# Trigger_Delay_Board.net
KiCad netlist of a schematic drawn in EAGLE
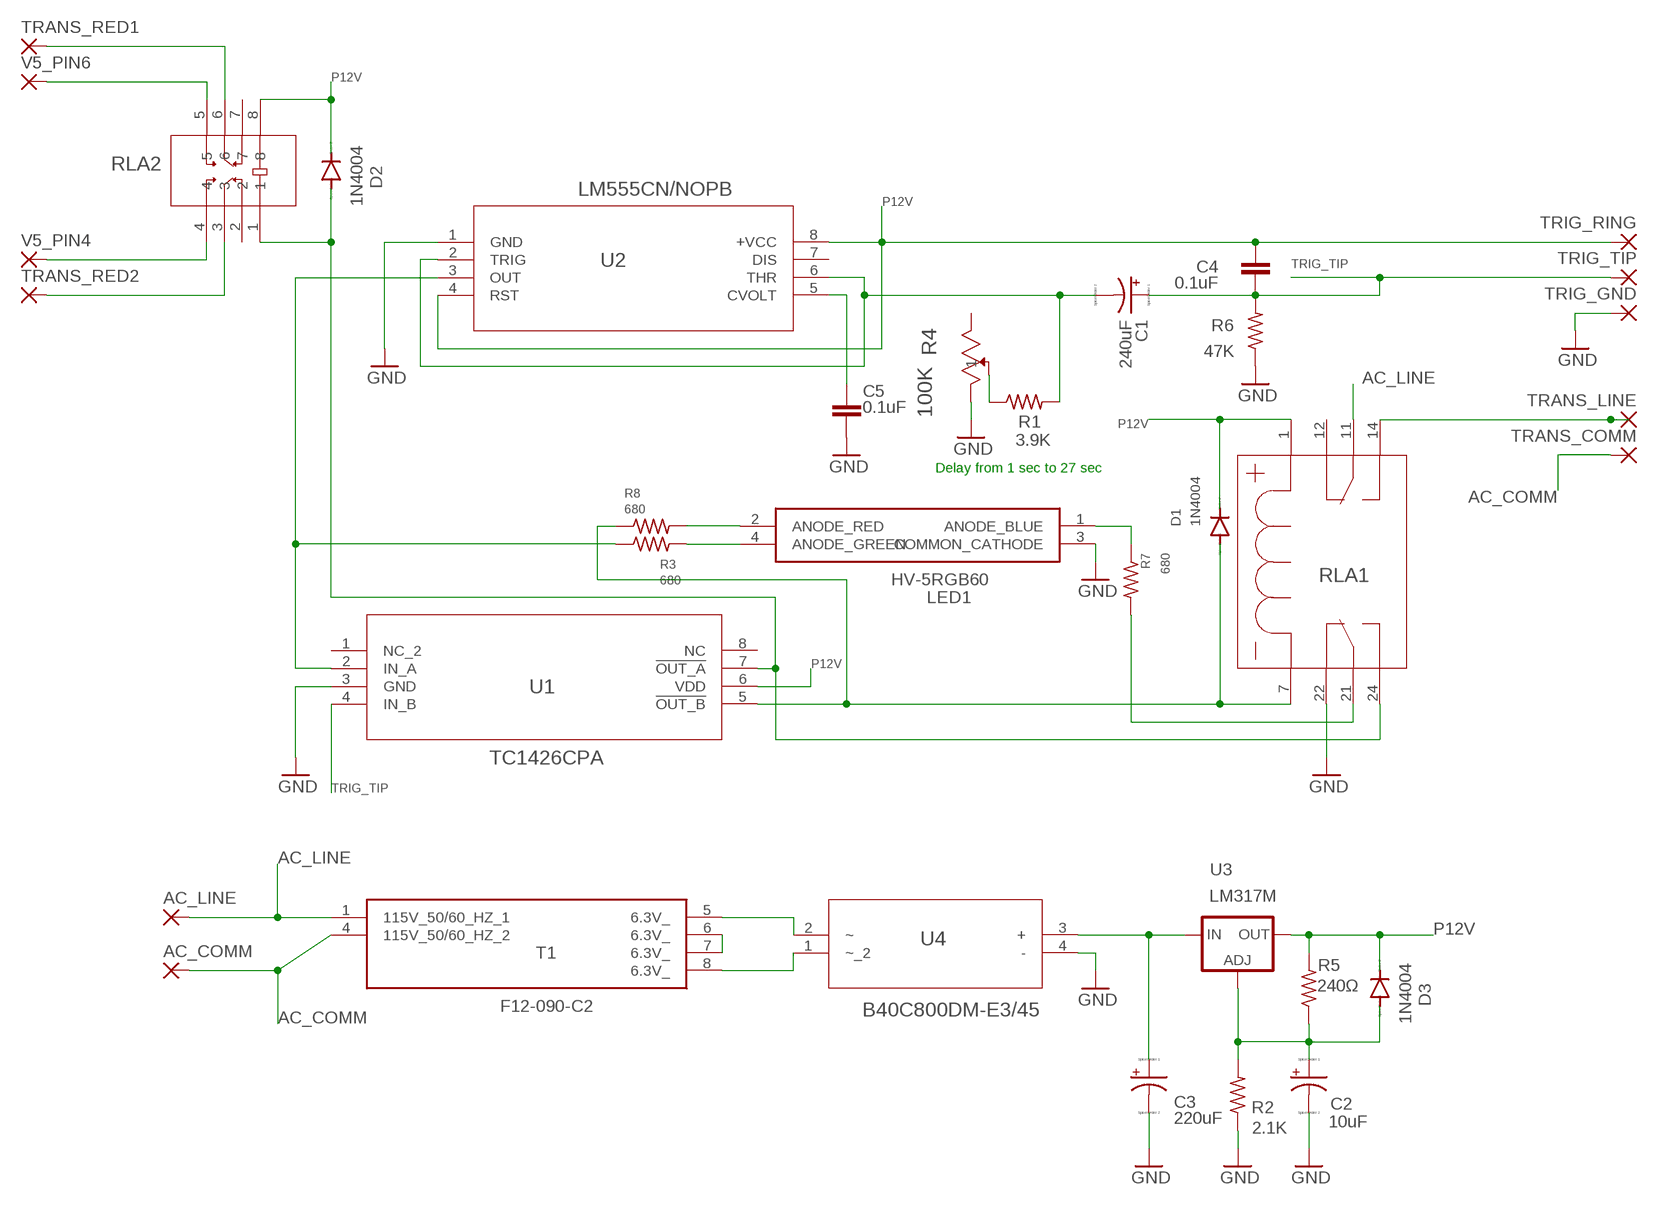
[diagram p0: schematic, sheet 1]

(export (version "E")
  (design (tool "Eeschema 10.0.6"))
  (components
    (comp (ref "AC_COMM")
      (value "3,81/1,4")
      (footprint "eagle-import:3,81_1,4")
      (libsource (lib "eagle-import") (part "3,81/1,4"))
    )
    (comp (ref "AC_LINE")
      (value "3,81/1,4")
      (footprint "eagle-import:3,81_1,4")
      (libsource (lib "eagle-import") (part "3,81/1,4"))
    )
    (comp (ref "C1")
      (value "240uF")
      (footprint "eagle-import:E1,8-4")
      (libsource (lib "eagle-import") (part "CPOL-USE1.8-4"))
    )
    (comp (ref "C2")
      (value "10uF")
      (footprint "eagle-import:E1,8-4")
      (libsource (lib "eagle-import") (part "CPOL-USE1.8-4"))
    )
    (comp (ref "C3")
      (value "220uF")
      (footprint "eagle-import:E1,8-4")
      (libsource (lib "eagle-import") (part "CPOL-USE1.8-4"))
    )
    (comp (ref "C4")
      (value "0.1uF")
      (footprint "eagle-import:C025-024X044")
      (libsource (lib "eagle-import") (part "C-EU025-024X044"))
    )
    (comp (ref "C5")
      (value "0.1uF")
      (footprint "eagle-import:C025-024X044")
      (libsource (lib "eagle-import") (part "C-EU025-024X044"))
    )
    (comp (ref "D1")
      (value "1N4004")
      (footprint "eagle-import:DO41-10")
      (libsource (lib "eagle-import") (part "1N4004"))
    )
    (comp (ref "D2")
      (value "1N4004")
      (footprint "eagle-import:DO41-10")
      (libsource (lib "eagle-import") (part "1N4004"))
    )
    (comp (ref "D3")
      (value "1N4004")
      (footprint "eagle-import:DO41-10")
      (libsource (lib "eagle-import") (part "1N4004"))
    )
    (comp (ref "LED1")
      (value "HV-5RGB60")
      (footprint "eagle-import:HV5RGB25")
      (fields (field (name "MOUSER_PART_NUMBER") "743-HV-5RGB60"))
      (libsource (lib "eagle-import") (part "HV-5RGB60"))
    )
    (comp (ref "R1")
      (value "3.9K")
      (footprint "eagle-import:0207_10")
      (libsource (lib "eagle-import") (part "R-US_0207/10"))
    )
    (comp (ref "R2")
      (value "2.1K")
      (footprint "eagle-import:0207_10")
      (libsource (lib "eagle-import") (part "R-US_0207/10"))
    )
    (comp (ref "R3")
      (value "680")
      (footprint "eagle-import:0207_10")
      (libsource (lib "eagle-import") (part "R-US_0207/10"))
    )
    (comp (ref "R4")
      (value "100K")
      (footprint "eagle-import:RES3_64W")
      (fields
        (field (name "MANUFACTURER_PART_NUMBER") "64WR100KLF")
        (field (name "COPYRIGHT") "Copyright (C) 2016 Accelerated Designs. All rights reserved")
      )
      (libsource (lib "eagle-import") (part "64WR100KLF"))
    )
    (comp (ref "R5")
      (value "240Ω")
      (footprint "eagle-import:0207_10")
      (libsource (lib "eagle-import") (part "R-US_0207/10"))
    )
    (comp (ref "R6")
      (value "47K")
      (footprint "eagle-import:0207_10")
      (libsource (lib "eagle-import") (part "R-US_0207/10"))
    )
    (comp (ref "R7")
      (value "680")
      (footprint "eagle-import:0207_10")
      (libsource (lib "eagle-import") (part "R-US_0207/10"))
    )
    (comp (ref "R8")
      (value "680")
      (footprint "eagle-import:0207_10")
      (libsource (lib "eagle-import") (part "R-US_0207/10"))
    )
    (comp (ref "RLA1")
      (value "RTE24012")
      (footprint "eagle-import:RELAY-DPDT_5MM")
      (fields (field (name "COPYRIGHT") "Copyright (C) 2016 Accelerated Designs. All rights reserved"))
      (libsource (lib "eagle-import") (part "RTE24012"))
    )
    (comp (ref "RLA2")
      (value "G2RL-2_DC12")
      (footprint "eagle-import:RELAY_G2RL-2")
      (fields
        (field (name "MANUFACTURER_PART_NUMBER") "G2RL-2 DC12")
        (field (name "COPYRIGHT") "Copyright (C) 2018 Accelerated Designs. All rights reserved")
      )
      (libsource (lib "eagle-import") (part "G2RL-2_DC12"))
    )
    (comp (ref "T1")
      (value "F12-090-C2")
      (footprint "eagle-import:F12090C2")
      (fields (field (name "MOUSER_PART_NUMBER") "553-F12-090-C2"))
      (libsource (lib "eagle-import") (part "F12-090-C2"))
    )
    (comp (ref "TRANS_COMM")
      (value "3,81/1,4")
      (footprint "eagle-import:3,81_1,4")
      (libsource (lib "eagle-import") (part "3,81/1,4"))
    )
    (comp (ref "TRANS_LINE")
      (value "3,81/1,4")
      (footprint "eagle-import:3,81_1,4")
      (libsource (lib "eagle-import") (part "3,81/1,4"))
    )
    (comp (ref "TRANS_RED1")
      (value "3,81/1,4")
      (footprint "eagle-import:3,81_1,4")
      (libsource (lib "eagle-import") (part "3,81/1,4"))
    )
    (comp (ref "TRANS_RED2")
      (value "3,81/1,4")
      (footprint "eagle-import:3,81_1,4")
      (libsource (lib "eagle-import") (part "3,81/1,4"))
    )
    (comp (ref "TRIG_GND")
      (value "3,81/1,4")
      (footprint "eagle-import:3,81_1,4")
      (libsource (lib "eagle-import") (part "3,81/1,4"))
    )
    (comp (ref "TRIG_RING")
      (value "3,81/1,4")
      (footprint "eagle-import:3,81_1,4")
      (libsource (lib "eagle-import") (part "3,81/1,4"))
    )
    (comp (ref "TRIG_TIP")
      (value "3,81/1,4")
      (footprint "eagle-import:3,81_1,4")
      (libsource (lib "eagle-import") (part "3,81/1,4"))
    )
    (comp (ref "U1")
      (value "TC1426CPA")
      (footprint "eagle-import:PDIP8_300MC")
      (libsource (lib "eagle-import") (part "TC1426CPA"))
    )
    (comp (ref "U2")
      (value "LM555CN/NOPB")
      (footprint "eagle-import:N08E")
      (libsource (lib "eagle-import") (part "LM555CN/NOPB"))
    )
    (comp (ref "U3")
      (value "LM317MB")
      (footprint "eagle-import:TO220L1")
      (fields (field (name "PARTNUMBER") "LM317M"))
      (libsource (lib "eagle-import") (part "LM317?MB"))
    )
    (comp (ref "U4")
      (value "B40C800DM-E3/45")
      (footprint "eagle-import:DIP4_DFM")
      (fields (field (name "SPICEPREFIX") "E"))
      (libsource (lib "eagle-import") (part "B40C800DM-E3/45"))
    )
    (comp (ref "V5_PIN4")
      (value "3,81/1,4")
      (footprint "eagle-import:3,81_1,4")
      (libsource (lib "eagle-import") (part "3,81/1,4"))
    )
    (comp (ref "V5_PIN6")
      (value "3,81/1,4")
      (footprint "eagle-import:3,81_1,4")
      (libsource (lib "eagle-import") (part "3,81/1,4"))
    )
  )
  (nets
    (net (code "1") (name "/AC_COMM") (class "Default")
      (node (ref "AC_COMM") (pin "1") (pinfunction "P_1") (pintype "passive"))
      (node (ref "T1") (pin "4") (pinfunction "115V_50/60_HZ_2_4") (pintype "bidirectional"))
      (node (ref "TRANS_COMM") (pin "1") (pinfunction "P_1") (pintype "passive"))
    )
    (net (code "2") (name "/AC_LINE") (class "Default")
      (node (ref "AC_LINE") (pin "1") (pinfunction "P_1") (pintype "passive"))
      (node (ref "RLA1") (pin "11") (pinfunction "3_11") (pintype "passive"))
      (node (ref "T1") (pin "1") (pinfunction "115V_50/60_HZ_1_1") (pintype "bidirectional"))
    )
    (net (code "3") (name "/P12V") (class "Default")
      (node (ref "C4") (pin "1") (pinfunction "1_1") (pintype "passive"))
      (node (ref "D1") (pin "C") (pinfunction "C_C") (pintype "passive"))
      (node (ref "D2") (pin "C") (pinfunction "C_C") (pintype "passive"))
      (node (ref "D3") (pin "C") (pinfunction "C_C") (pintype "passive"))
      (node (ref "R5") (pin "2") (pinfunction "2_2") (pintype "passive"))
      (node (ref "RLA1") (pin "1") (pinfunction "1_1") (pintype "passive"))
      (node (ref "RLA2") (pin "8") (pinfunction "8_8") (pintype "passive"))
      (node (ref "TRIG_RING") (pin "1") (pinfunction "P_1") (pintype "passive"))
      (node (ref "U1") (pin "6") (pinfunction "VDD_6") (pintype "passive"))
      (node (ref "U2") (pin "4") (pinfunction "RST_4") (pintype "input"))
      (node (ref "U2") (pin "8") (pinfunction "+VCC_8") (pintype "power_in"))
      (node (ref "U3") (pin "2") (pinfunction "OUT_2") (pintype "passive"))
    )
    (net (code "4") (name "/TRIG_TIP") (class "Default")
      (node (ref "C1") (pin "+") (pinfunction "+_+") (pintype "passive"))
      (node (ref "C4") (pin "2") (pinfunction "2_2") (pintype "passive"))
      (node (ref "R6") (pin "2") (pinfunction "2_2") (pintype "passive"))
      (node (ref "TRIG_TIP") (pin "1") (pinfunction "P_1") (pintype "passive"))
      (node (ref "U1") (pin "4") (pinfunction "IN_B_4") (pintype "input"))
    )
    (net (code "5") (name "GND") (class "Default")
      (node (ref "C2") (pin "-") (pinfunction "-_-") (pintype "passive"))
      (node (ref "C3") (pin "-") (pinfunction "-_-") (pintype "passive"))
      (node (ref "C5") (pin "2") (pinfunction "2_2") (pintype "passive"))
      (node (ref "LED1") (pin "3") (pinfunction "COMMON_CATHODE_3") (pintype "bidirectional"))
      (node (ref "R2") (pin "1") (pinfunction "1_1") (pintype "passive"))
      (node (ref "R4") (pin "1") (pinfunction "1_1") (pintype "passive"))
      (node (ref "R6") (pin "1") (pinfunction "1_1") (pintype "passive"))
      (node (ref "RLA1") (pin "22") (pinfunction "7_22") (pintype "passive"))
      (node (ref "TRIG_GND") (pin "1") (pinfunction "P_1") (pintype "passive"))
      (node (ref "U1") (pin "3") (pinfunction "GND_3") (pintype "passive"))
      (node (ref "U2") (pin "1") (pinfunction "GND_1") (pintype "power_in"))
      (node (ref "U4") (pin "4") (pinfunction "-_4") (pintype "passive"))
    )
    (net (code "6") (name "Net-(LED1-ANODE_BLUE)") (class "Default")
      (node (ref "LED1") (pin "1") (pinfunction "ANODE_BLUE_1") (pintype "bidirectional"))
      (node (ref "R7") (pin "1") (pinfunction "1_1") (pintype "passive"))
    )
    (net (code "7") (name "Net-(LED1-ANODE_GREEN)") (class "Default")
      (node (ref "LED1") (pin "4") (pinfunction "ANODE_GREEN_4") (pintype "bidirectional"))
      (node (ref "R3") (pin "2") (pinfunction "2_2") (pintype "passive"))
    )
    (net (code "8") (name "Net-(LED1-ANODE_RED)") (class "Default")
      (node (ref "LED1") (pin "2") (pinfunction "ANODE_RED_2") (pintype "bidirectional"))
      (node (ref "R8") (pin "2") (pinfunction "2_2") (pintype "passive"))
    )
    (net (code "9") (name "Net-(R1-Pad1)") (class "Default")
      (node (ref "R1") (pin "1") (pinfunction "1_1") (pintype "passive"))
      (node (ref "R4") (pin "2") (pinfunction "2_2") (pintype "passive"))
    )
    (net (code "10") (name "Net-(RLA1-4)") (class "Default")
      (node (ref "RLA1") (pin "14") (pinfunction "4_14") (pintype "passive"))
      (node (ref "TRANS_LINE") (pin "1") (pinfunction "P_1") (pintype "passive"))
    )
    (net (code "11") (name "Net-(RLA1-5)") (class "Default")
      (node (ref "D2") (pin "A") (pinfunction "A_A") (pintype "passive"))
      (node (ref "RLA1") (pin "24") (pinfunction "5_24") (pintype "passive"))
      (node (ref "RLA2") (pin "1") (pinfunction "1_1") (pintype "passive"))
      (node (ref "U1") (pin "7") (pinfunction "~{OUT_A}_7") (pintype "output"))
    )
    (net (code "12") (name "Net-(RLA1-6)") (class "Default")
      (node (ref "R7") (pin "2") (pinfunction "2_2") (pintype "passive"))
      (node (ref "RLA1") (pin "21") (pinfunction "6_21") (pintype "passive"))
    )
    (net (code "13") (name "Net-(RLA1-8)") (class "Default")
      (node (ref "D1") (pin "A") (pinfunction "A_A") (pintype "passive"))
      (node (ref "R8") (pin "1") (pinfunction "1_1") (pintype "passive"))
      (node (ref "RLA1") (pin "7") (pinfunction "8_7") (pintype "passive"))
      (node (ref "U1") (pin "5") (pinfunction "~{OUT_B}_5") (pintype "output"))
    )
    (net (code "14") (name "Net-(T1-6.3V_-Pad6)") (class "Default")
      (node (ref "T1") (pin "6") (pinfunction "6.3V__6") (pintype "bidirectional"))
      (node (ref "T1") (pin "7") (pinfunction "6.3V__7") (pintype "bidirectional"))
    )
    (net (code "15") (name "Net-(TRANS_RED1-P)") (class "Default")
      (node (ref "RLA2") (pin "6") (pinfunction "6_6") (pintype "passive"))
      (node (ref "TRANS_RED1") (pin "1") (pinfunction "P_1") (pintype "passive"))
    )
    (net (code "16") (name "Net-(TRANS_RED2-P)") (class "Default")
      (node (ref "RLA2") (pin "3") (pinfunction "3_3") (pintype "passive"))
      (node (ref "TRANS_RED2") (pin "1") (pinfunction "P_1") (pintype "passive"))
    )
    (net (code "17") (name "Net-(U1-IN_A)") (class "Default")
      (node (ref "R3") (pin "1") (pinfunction "1_1") (pintype "passive"))
      (node (ref "U1") (pin "2") (pinfunction "IN_A_2") (pintype "input"))
      (node (ref "U2") (pin "3") (pinfunction "OUT_3") (pintype "output"))
    )
    (net (code "18") (name "Net-(U2-CVOLT)") (class "Default")
      (node (ref "C5") (pin "1") (pinfunction "1_1") (pintype "passive"))
      (node (ref "U2") (pin "5") (pinfunction "CVOLT_5") (pintype "passive"))
    )
    (net (code "19") (name "Net-(U2-THR)") (class "Default")
      (node (ref "C1") (pin "-") (pinfunction "-_-") (pintype "passive"))
      (node (ref "R1") (pin "2") (pinfunction "2_2") (pintype "passive"))
      (node (ref "U2") (pin "2") (pinfunction "TRIG_2") (pintype "input"))
      (node (ref "U2") (pin "6") (pinfunction "THR_6") (pintype "input"))
    )
    (net (code "20") (name "Net-(U3-ADJ)") (class "Default")
      (node (ref "C2") (pin "+") (pinfunction "+_+") (pintype "passive"))
      (node (ref "D3") (pin "A") (pinfunction "A_A") (pintype "passive"))
      (node (ref "R2") (pin "2") (pinfunction "2_2") (pintype "passive"))
      (node (ref "R5") (pin "1") (pinfunction "1_1") (pintype "passive"))
      (node (ref "U3") (pin "1") (pinfunction "ADJ_1") (pintype "input"))
    )
    (net (code "21") (name "Net-(U3-IN)") (class "Default")
      (node (ref "C3") (pin "+") (pinfunction "+_+") (pintype "passive"))
      (node (ref "U3") (pin "3") (pinfunction "IN_3") (pintype "input"))
      (node (ref "U4") (pin "3") (pinfunction "+_3") (pintype "passive"))
    )
    (net (code "22") (name "Net-(U4-~)") (class "Default")
      (node (ref "T1") (pin "5") (pinfunction "6.3V__5") (pintype "bidirectional"))
      (node (ref "U4") (pin "2") (pinfunction "~_2") (pintype "passive"))
    )
    (net (code "23") (name "Net-(U4-~{_2})") (class "Default")
      (node (ref "T1") (pin "8") (pinfunction "6.3V__8") (pintype "bidirectional"))
      (node (ref "U4") (pin "1") (pinfunction "~{_2}_1") (pintype "passive"))
    )
    (net (code "24") (name "Net-(V5_PIN4-P)") (class "Default")
      (node (ref "RLA2") (pin "4") (pinfunction "4_4") (pintype "passive"))
      (node (ref "V5_PIN4") (pin "1") (pinfunction "P_1") (pintype "passive"))
    )
    (net (code "25") (name "Net-(V5_PIN6-P)") (class "Default")
      (node (ref "RLA2") (pin "5") (pinfunction "5_5") (pintype "passive"))
      (node (ref "V5_PIN6") (pin "1") (pinfunction "P_1") (pintype "passive"))
    )
    (net (code "26") (name "unconnected-(R4-Pad3)") (class "Default")
      (node (ref "R4") (pin "3") (pinfunction "3_3") (pintype "passive"))
    )
    (net (code "27") (name "unconnected-(RLA1-2-Pad12)") (class "Default")
      (node (ref "RLA1") (pin "12") (pinfunction "2_12") (pintype "passive"))
    )
    (net (code "28") (name "unconnected-(RLA2-Pad2)") (class "Default")
      (node (ref "RLA2") (pin "2") (pinfunction "2_2") (pintype "passive"))
    )
    (net (code "29") (name "unconnected-(RLA2-Pad7)") (class "Default")
      (node (ref "RLA2") (pin "7") (pinfunction "7_7") (pintype "passive"))
    )
    (net (code "30") (name "unconnected-(U1-NC-Pad8)") (class "Default")
      (node (ref "U1") (pin "8") (pinfunction "NC_8") (pintype "no_connect"))
    )
    (net (code "31") (name "unconnected-(U1-NC_2-Pad1)") (class "Default")
      (node (ref "U1") (pin "1") (pinfunction "NC_2_1") (pintype "no_connect"))
    )
    (net (code "32") (name "unconnected-(U2-DIS-Pad7)") (class "Default")
      (node (ref "U2") (pin "7") (pinfunction "DIS_7") (pintype "passive"))
    )
  )
)
